# LoRa.net
KiCad netlist of a schematic drawn in Altium Designer
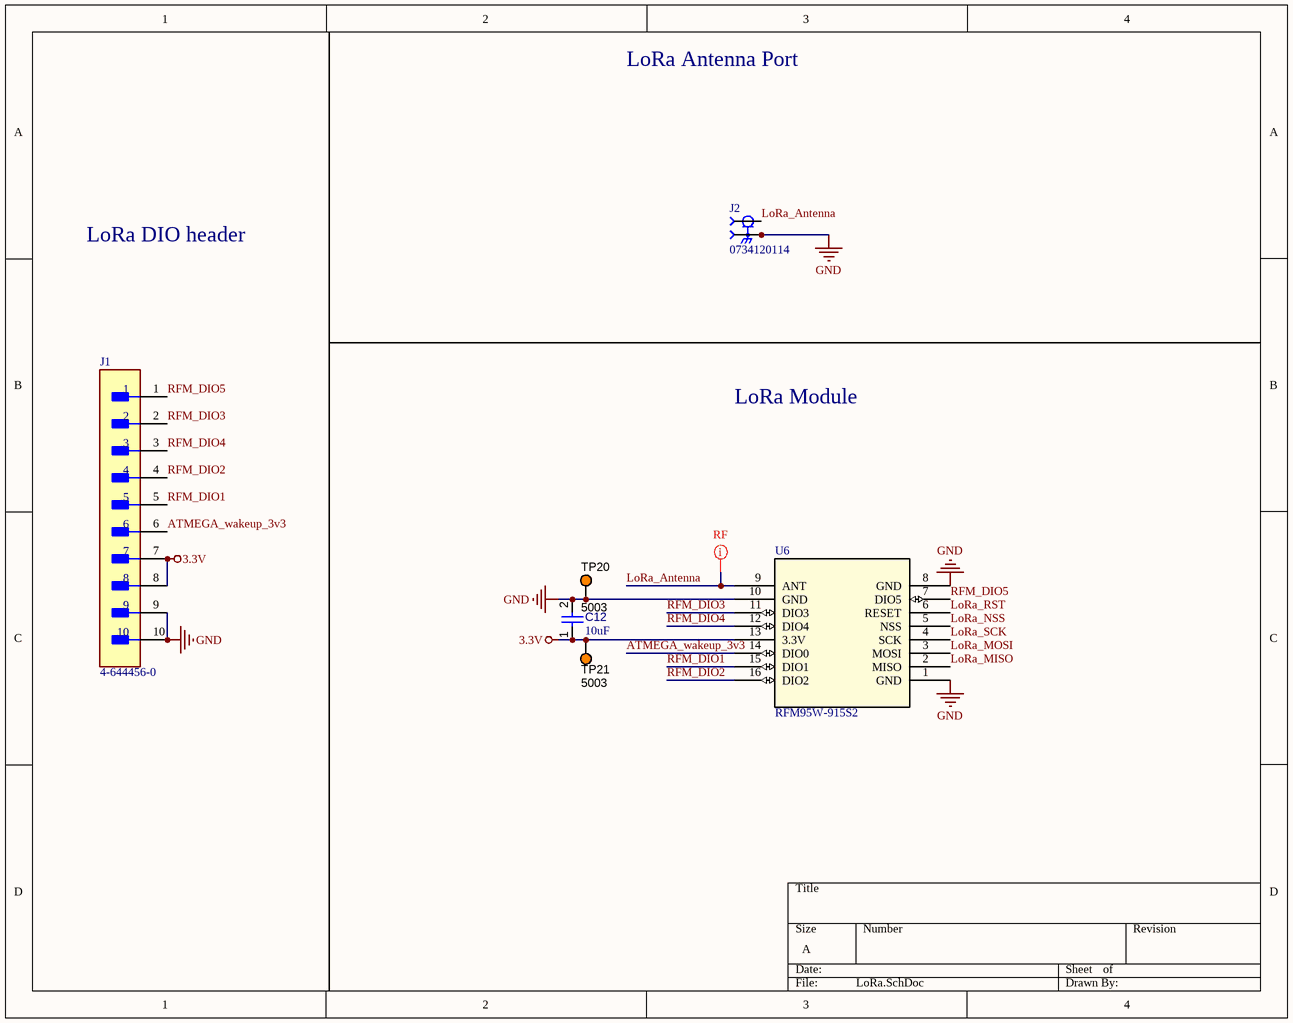
[diagram p0: LoRa.SchDoc]

(export (version "E")
  (design (tool "Eeschema 10.0.6"))
  (components
    (comp (ref "C12")
      (value "10uF")
      (footprint "CAPC1608X90X40NL10T20")
      (description "Chip Capacitor, 100 nF, +/- 10%, 50 V, 0603 (1608 Metric)")
      (fields (field (name "TOLERANCE") "10%") (field (name "Comment") "Capacitor 100 nF +/-10% 50 V 0603"))
      (libsource (lib "University of Michigan") (part "CAP-NP-2"))
    )
    (comp (ref "J1")
      (value "4-644456-0")
      (footprint "FP-4-644456-0-MFG")
      (libsource (lib "University of Michigan") (part "aee40dc8b284c03a16094555aa210be"))
    )
    (comp (ref "J2")
      (value "0734120114")
      (footprint "MOLEX_0734120114")
      (description "U.FL (UMCC) Connector Receptacle, Male Pin 50Ohm Surface Mount Solder")
      (fields (field (name "MF") "Molex"))
      (libsource (lib "University of Michigan") (part "0734120114"))
    )
    (comp (ref "TP20")
      (value "5003")
      (footprint "KSTN-5003")
      (description "Test Point, Orange, Height 4.6 mm, Tail Length 3 mm, 1-Pin THD, RoHS")
      (fields (field (name "MANUFACTURER") "Keystone"))
      (libsource (lib "University of Michigan") (part "TESTPOINT_ORANGE"))
    )
    (comp (ref "TP21")
      (value "5003")
      (footprint "KSTN-5003")
      (description "Test Point, Orange, Height 4.6 mm, Tail Length 3 mm, 1-Pin THD, RoHS")
      (fields (field (name "MANUFACTURER") "Keystone"))
      (libsource (lib "University of Michigan") (part "TESTPOINT_ORANGE"))
    )
    (comp (ref "U6")
      (value "RFM95W-915S2")
      (footprint "IC16_RFM95W-915S2_RFS")
      (description "No Description Available")
      (fields (field (name "COPYRIGHT") "Copyright (C) 2023 Ultra Librarian. All rights reserved."))
      (libsource (lib "University of Michigan") (part "RFM95W-915S2"))
    )
  )
  (nets
    (net (code "1") (name "/ATMEGA_wakeup_3v3") (class "Default")
      (node (ref "J1") (pin "6") (pinfunction "6_6") (pintype "passive"))
      (node (ref "U6") (pin "14") (pinfunction "DIO0_14") (pintype "bidirectional"))
    )
    (net (code "2") (name "/LoRa_Antenna") (class "Default")
      (node (ref "J2") (pin "1") (pinfunction "SIG_1") (pintype "passive"))
      (node (ref "U6") (pin "9") (pinfunction "ANT_9") (pintype "passive"))
    )
    (net (code "3") (name "/LoRa_MISO") (class "Default")
      (node (ref "U6") (pin "2") (pinfunction "MISO_2") (pintype "passive"))
    )
    (net (code "4") (name "/LoRa_MOSI") (class "Default")
      (node (ref "U6") (pin "3") (pinfunction "MOSI_3") (pintype "passive"))
    )
    (net (code "5") (name "/LoRa_NSS") (class "Default")
      (node (ref "U6") (pin "5") (pinfunction "NSS_5") (pintype "passive"))
    )
    (net (code "6") (name "/LoRa_RST") (class "Default")
      (node (ref "U6") (pin "6") (pinfunction "RESET_6") (pintype "passive"))
    )
    (net (code "7") (name "/LoRa_SCK") (class "Default")
      (node (ref "U6") (pin "4") (pinfunction "SCK_4") (pintype "passive"))
    )
    (net (code "8") (name "/RFM_DIO1") (class "Default")
      (node (ref "J1") (pin "5") (pinfunction "5_5") (pintype "passive"))
      (node (ref "U6") (pin "15") (pinfunction "DIO1_15") (pintype "bidirectional"))
    )
    (net (code "9") (name "/RFM_DIO2") (class "Default")
      (node (ref "J1") (pin "4") (pinfunction "4_4") (pintype "passive"))
      (node (ref "U6") (pin "16") (pinfunction "DIO2_16") (pintype "bidirectional"))
    )
    (net (code "10") (name "/RFM_DIO3") (class "Default")
      (node (ref "J1") (pin "2") (pinfunction "2_2") (pintype "passive"))
      (node (ref "U6") (pin "11") (pinfunction "DIO3_11") (pintype "bidirectional"))
    )
    (net (code "11") (name "/RFM_DIO4") (class "Default")
      (node (ref "J1") (pin "3") (pinfunction "3_3") (pintype "passive"))
      (node (ref "U6") (pin "12") (pinfunction "DIO4_12") (pintype "bidirectional"))
    )
    (net (code "12") (name "/RFM_DIO5") (class "Default")
      (node (ref "J1") (pin "1") (pinfunction "1_1") (pintype "passive"))
      (node (ref "U6") (pin "7") (pinfunction "DIO5_7") (pintype "bidirectional"))
    )
    (net (code "13") (name "3.3V") (class "Default")
      (node (ref "C12") (pin "1") (pinfunction "1_1") (pintype "passive"))
      (node (ref "J1") (pin "7") (pinfunction "7_7") (pintype "passive"))
      (node (ref "J1") (pin "8") (pinfunction "8_8") (pintype "passive"))
      (node (ref "TP21") (pin "1") (pinfunction "1_1") (pintype "passive"))
      (node (ref "U6") (pin "13") (pinfunction "3.3V_13") (pintype "passive"))
    )
    (net (code "14") (name "GND") (class "Default")
      (node (ref "C12") (pin "2") (pinfunction "2_2") (pintype "passive"))
      (node (ref "J1") (pin "10") (pinfunction "10_10") (pintype "passive"))
      (node (ref "J1") (pin "9") (pinfunction "9_9") (pintype "passive"))
      (node (ref "J2") (pin "2") (pinfunction "GND_2") (pintype "power_in"))
      (node (ref "J2") (pin "3") (pinfunction "GND_3") (pintype "power_in"))
      (node (ref "J2") (pin "4") (pinfunction "GND_4") (pintype "power_in"))
      (node (ref "TP20") (pin "1") (pinfunction "1_1") (pintype "passive"))
      (node (ref "U6") (pin "1") (pinfunction "GND_1") (pintype "power_in"))
      (node (ref "U6") (pin "10") (pinfunction "GND_10") (pintype "power_in"))
      (node (ref "U6") (pin "8") (pinfunction "GND_8") (pintype "power_in"))
    )
  )
)
